# DoubleMotorSwitch.net
KiCad netlist of a schematic drawn in EAGLE
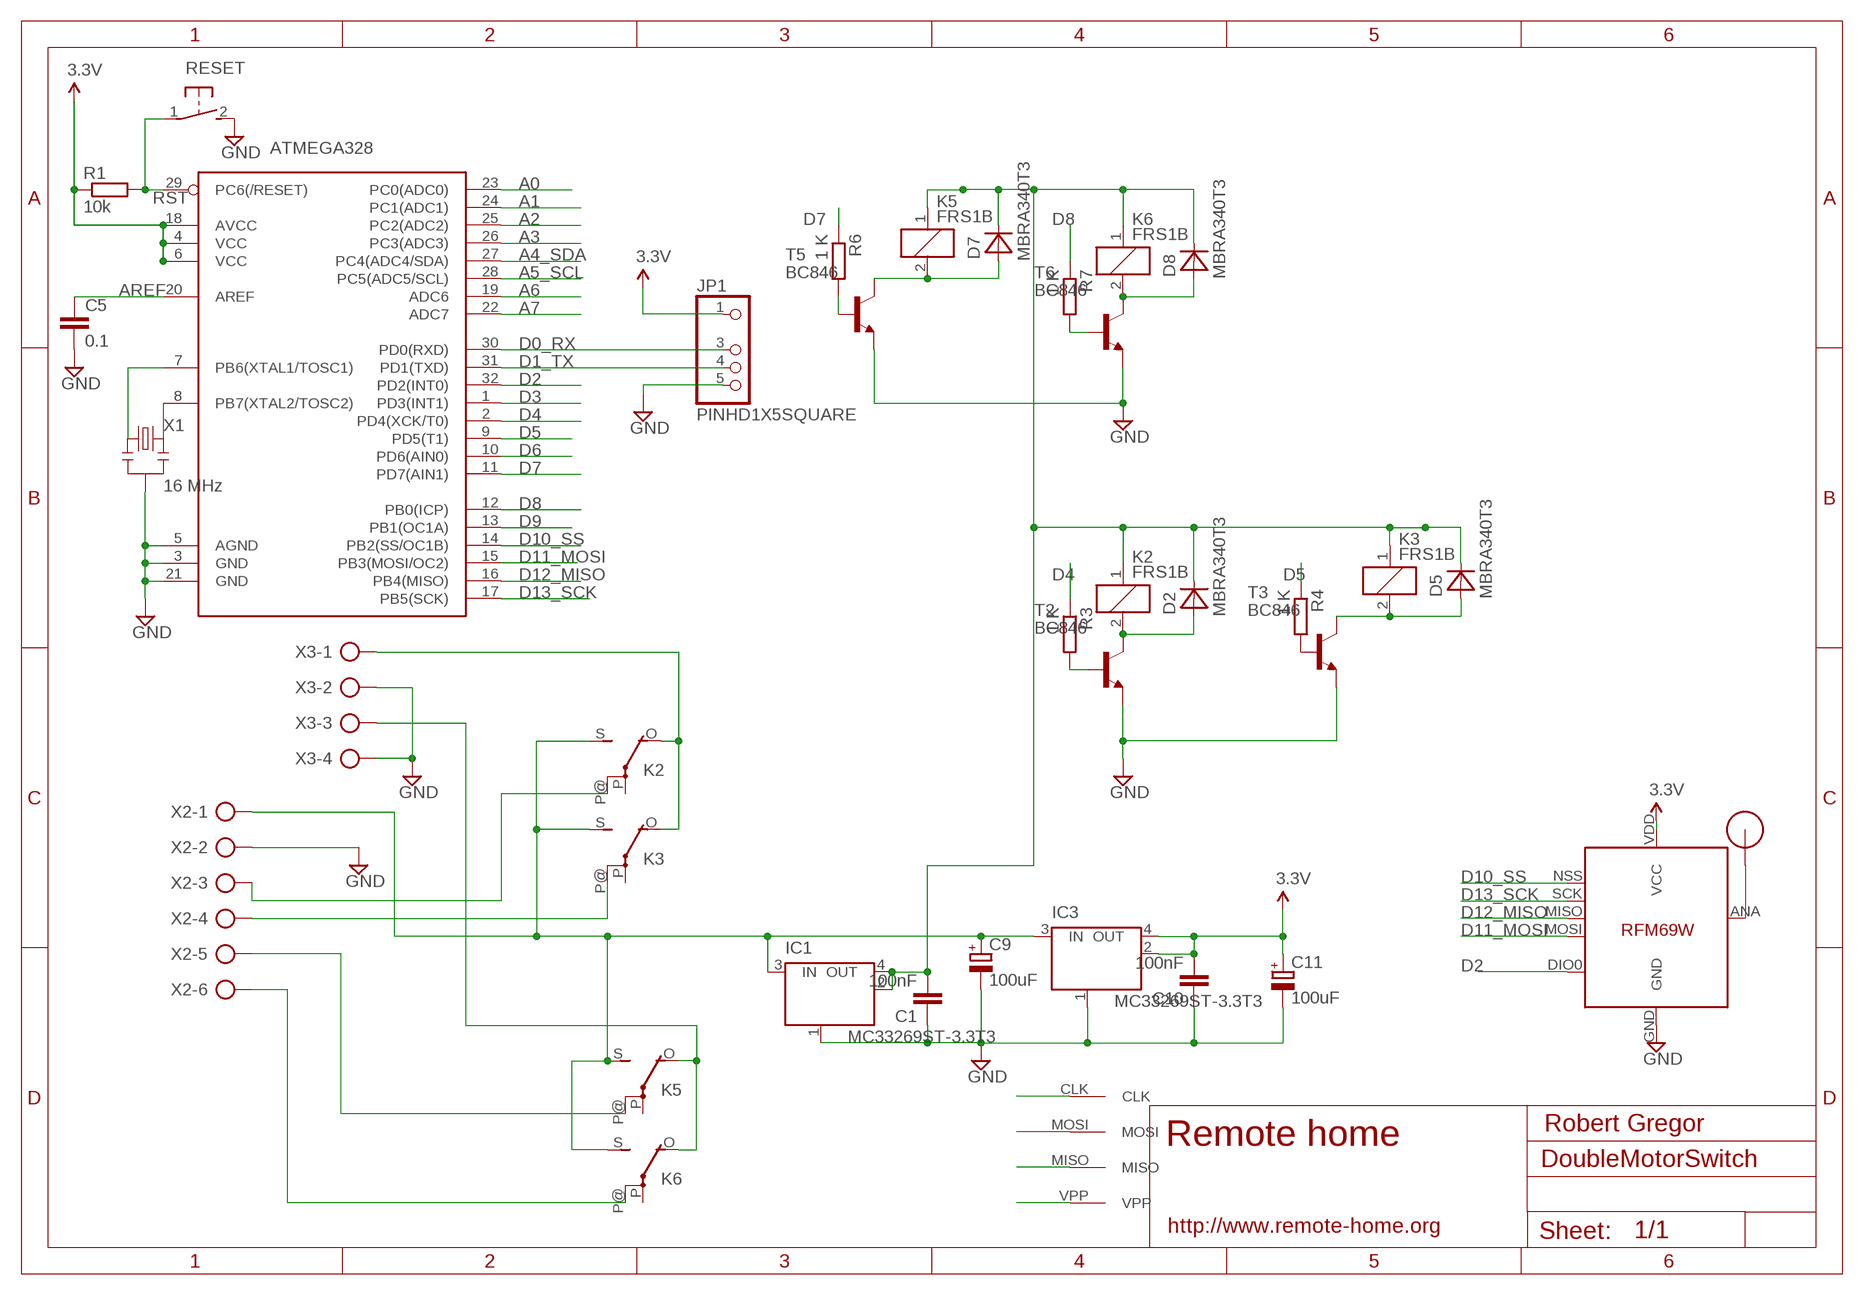
[diagram p0: schematic, sheet 1]

(export (version "E")
  (design (tool "Eeschema 10.0.6"))
  (components
    (comp (ref "ATMEGA328")
      (value "ATMega-328")
      (footprint "eagle-import:TQFP32-08")
      (libsource (lib "eagle-import") (part "ATMEGA168/328TQFP32"))
    )
    (comp (ref "C1")
      (value "100nF")
      (footprint "eagle-import:C2012")
      (libsource (lib "eagle-import") (part "C-EUC2012"))
    )
    (comp (ref "C5")
      (value "0.1")
      (footprint "eagle-import:C2012")
      (libsource (lib "eagle-import") (part "C-EUC2012"))
    )
    (comp (ref "C9")
      (value "100uF")
      (footprint "eagle-import:SMC_B")
      (libsource (lib "eagle-import") (part "CPOL-EUSMCB"))
    )
    (comp (ref "C10")
      (value "100nF")
      (footprint "eagle-import:C2012")
      (libsource (lib "eagle-import") (part "C-EUC2012"))
    )
    (comp (ref "C11")
      (value "100uF")
      (footprint "eagle-import:SMC_B")
      (libsource (lib "eagle-import") (part "CPOL-EUSMCB"))
    )
    (comp (ref "D2")
      (value "MBRA340T3")
      (footprint "eagle-import:SMA")
      (libsource (lib "eagle-import") (part "MBRA340T3"))
    )
    (comp (ref "D5")
      (value "MBRA340T3")
      (footprint "eagle-import:SMA")
      (libsource (lib "eagle-import") (part "MBRA340T3"))
    )
    (comp (ref "D7")
      (value "MBRA340T3")
      (footprint "eagle-import:SMA")
      (libsource (lib "eagle-import") (part "MBRA340T3"))
    )
    (comp (ref "D8")
      (value "MBRA340T3")
      (footprint "eagle-import:SMA")
      (libsource (lib "eagle-import") (part "MBRA340T3"))
    )
    (comp (ref "IC1")
      (value "MC33269ST-3.3T3")
      (footprint "eagle-import:SOT223")
      (libsource (lib "eagle-import") (part "MC33269ST-3.3T3"))
    )
    (comp (ref "IC3")
      (value "MC33269ST-3.3T3")
      (footprint "eagle-import:SOT223")
      (libsource (lib "eagle-import") (part "MC33269ST-3.3T3"))
    )
    (comp (ref "JP1")
      (value "PINHD1X5SQUARE")
      (footprint "eagle-import:PINHD1X05-SQUARE")
      (libsource (lib "eagle-import") (part "PINHD1X5SQUARE"))
    )
    (comp (ref "K2")
      (value "FRS1B")
      (footprint "eagle-import:FRS1B")
      (libsource (lib "eagle-import") (part "FRS1B"))
    )
    (comp (ref "K3")
      (value "FRS1B")
      (footprint "eagle-import:FRS1B")
      (libsource (lib "eagle-import") (part "FRS1B"))
    )
    (comp (ref "K5")
      (value "FRS1B")
      (footprint "eagle-import:FRS1B")
      (libsource (lib "eagle-import") (part "FRS1B"))
    )
    (comp (ref "K6")
      (value "FRS1B")
      (footprint "eagle-import:FRS1B")
      (libsource (lib "eagle-import") (part "FRS1B"))
    )
    (comp (ref "R1")
      (value "10k")
      (footprint "eagle-import:R2012")
      (libsource (lib "eagle-import") (part "R-EU_R2012"))
    )
    (comp (ref "R3")
      (value "1 K")
      (footprint "eagle-import:M2012")
      (libsource (lib "eagle-import") (part "R-EU_M2012"))
    )
    (comp (ref "R4")
      (value "1 K")
      (footprint "eagle-import:M2012")
      (libsource (lib "eagle-import") (part "R-EU_M2012"))
    )
    (comp (ref "R6")
      (value "1 K")
      (footprint "eagle-import:M2012")
      (libsource (lib "eagle-import") (part "R-EU_M2012"))
    )
    (comp (ref "R7")
      (value "1 K")
      (footprint "eagle-import:M2012")
      (libsource (lib "eagle-import") (part "R-EU_M2012"))
    )
    (comp (ref "RESET")
      (value "DTSM-3")
      (footprint "eagle-import:DTSM-3")
      (libsource (lib "eagle-import") (part "DTSM-3"))
    )
    (comp (ref "T2")
      (value "BC846")
      (footprint "eagle-import:SOT23")
      (libsource (lib "eagle-import") (part "BC846"))
    )
    (comp (ref "T3")
      (value "BC846")
      (footprint "eagle-import:SOT23")
      (libsource (lib "eagle-import") (part "BC846"))
    )
    (comp (ref "T5")
      (value "BC846")
      (footprint "eagle-import:SOT23")
      (libsource (lib "eagle-import") (part "BC846"))
    )
    (comp (ref "T6")
      (value "BC846")
      (footprint "eagle-import:SOT23")
      (libsource (lib "eagle-import") (part "BC846"))
    )
    (comp (ref "U$1")
      (value "RFM12B_ANTENNA")
      (footprint "eagle-import:RFM12B-ANTENNA")
      (libsource (lib "eagle-import") (part "RFM12B_ANTENNA"))
    )
    (comp (ref "U$2")
      (value "AVRHEADERDIP")
      (footprint "eagle-import:AVRHEADER")
      (libsource (lib "eagle-import") (part "AVRHEADERDIP"))
    )
    (comp (ref "U$5")
      (value "RFM69")
      (footprint "eagle-import:RFM69W-MINPADS")
      (libsource (lib "eagle-import") (part "RFM69"))
    )
    (comp (ref "X1")
      (value "16 MHz")
      (footprint "eagle-import:RESONATOR-SMD")
      (libsource (lib "eagle-import") (part "RESONATORSMD"))
    )
    (comp (ref "X2")
      (value "AK500/6")
      (footprint "eagle-import:AK500_6")
      (libsource (lib "eagle-import") (part "AK500/6"))
    )
    (comp (ref "X3")
      (value "AK500/4")
      (footprint "eagle-import:AK500_4")
      (libsource (lib "eagle-import") (part "AK500/4"))
    )
  )
  (nets
    (net (code "1") (name "/A0") (class "Default")
      (node (ref "ATMEGA328") (pin "23") (pinfunction "PC0(ADC0)_23") (pintype "bidirectional"))
    )
    (net (code "2") (name "/A1") (class "Default")
      (node (ref "ATMEGA328") (pin "24") (pinfunction "PC1(ADC1)_24") (pintype "bidirectional"))
    )
    (net (code "3") (name "/A2") (class "Default")
      (node (ref "ATMEGA328") (pin "25") (pinfunction "PC2(ADC2)_25") (pintype "bidirectional"))
    )
    (net (code "4") (name "/A3") (class "Default")
      (node (ref "ATMEGA328") (pin "26") (pinfunction "PC3(ADC3)_26") (pintype "bidirectional"))
    )
    (net (code "5") (name "/A4_SDA") (class "Default")
      (node (ref "ATMEGA328") (pin "27") (pinfunction "PC4(ADC4/SDA)_27") (pintype "bidirectional"))
    )
    (net (code "6") (name "/A5_SCL") (class "Default")
      (node (ref "ATMEGA328") (pin "28") (pinfunction "PC5(ADC5/SCL)_28") (pintype "bidirectional"))
    )
    (net (code "7") (name "/A6") (class "Default")
      (node (ref "ATMEGA328") (pin "19") (pinfunction "ADC6_19") (pintype "bidirectional"))
    )
    (net (code "8") (name "/A7") (class "Default")
      (node (ref "ATMEGA328") (pin "22") (pinfunction "ADC7_22") (pintype "bidirectional"))
    )
    (net (code "9") (name "/AREF") (class "Default")
      (node (ref "ATMEGA328") (pin "20") (pinfunction "AREF_20") (pintype "bidirectional"))
      (node (ref "C5") (pin "1") (pinfunction "1_1") (pintype "passive"))
    )
    (net (code "10") (name "/D0_RX") (class "Default")
      (node (ref "ATMEGA328") (pin "30") (pinfunction "PD0(RXD)_30") (pintype "bidirectional"))
      (node (ref "JP1") (pin "3") (pinfunction "3_3") (pintype "passive"))
    )
    (net (code "11") (name "/D1_TX") (class "Default")
      (node (ref "ATMEGA328") (pin "31") (pinfunction "PD1(TXD)_31") (pintype "bidirectional"))
      (node (ref "JP1") (pin "4") (pinfunction "4_4") (pintype "passive"))
    )
    (net (code "12") (name "/D2") (class "Default")
      (node (ref "ATMEGA328") (pin "32") (pinfunction "PD2(INT0)_32") (pintype "bidirectional"))
      (node (ref "U$5") (pin "DIO0") (pinfunction "DIO0_DIO0") (pintype "open_collector"))
    )
    (net (code "13") (name "/D3") (class "Default")
      (node (ref "ATMEGA328") (pin "1") (pinfunction "PD3(INT1)_1") (pintype "bidirectional"))
    )
    (net (code "14") (name "/D4") (class "Default")
      (node (ref "ATMEGA328") (pin "2") (pinfunction "PD4(XCK/T0)_2") (pintype "bidirectional"))
      (node (ref "R3") (pin "1") (pinfunction "1_1") (pintype "passive"))
    )
    (net (code "15") (name "/D5") (class "Default")
      (node (ref "ATMEGA328") (pin "9") (pinfunction "PD5(T1)_9") (pintype "bidirectional"))
      (node (ref "R4") (pin "1") (pinfunction "1_1") (pintype "passive"))
    )
    (net (code "16") (name "/D6") (class "Default")
      (node (ref "ATMEGA328") (pin "10") (pinfunction "PD6(AIN0)_10") (pintype "bidirectional"))
    )
    (net (code "17") (name "/D7") (class "Default")
      (node (ref "ATMEGA328") (pin "11") (pinfunction "PD7(AIN1)_11") (pintype "bidirectional"))
      (node (ref "R6") (pin "1") (pinfunction "1_1") (pintype "passive"))
    )
    (net (code "18") (name "/D8") (class "Default")
      (node (ref "ATMEGA328") (pin "12") (pinfunction "PB0(ICP)_12") (pintype "bidirectional"))
      (node (ref "R7") (pin "1") (pinfunction "1_1") (pintype "passive"))
    )
    (net (code "19") (name "/D9") (class "Default")
      (node (ref "ATMEGA328") (pin "13") (pinfunction "PB1(OC1A)_13") (pintype "bidirectional"))
    )
    (net (code "20") (name "/D10_SS") (class "Default")
      (node (ref "ATMEGA328") (pin "14") (pinfunction "PB2(SS/OC1B)_14") (pintype "bidirectional"))
      (node (ref "U$5") (pin "NSS") (pinfunction "SEL_NSS") (pintype "input"))
    )
    (net (code "21") (name "/D11_MOSI") (class "Default")
      (node (ref "ATMEGA328") (pin "15") (pinfunction "PB3(MOSI/OC2)_15") (pintype "bidirectional"))
      (node (ref "U$2") (pin "MOSI") (pinfunction "MOSI_MOSI") (pintype "bidirectional"))
      (node (ref "U$5") (pin "MOSI") (pinfunction "MOSI_MOSI") (pintype "output"))
    )
    (net (code "22") (name "/D12_MISO") (class "Default")
      (node (ref "ATMEGA328") (pin "16") (pinfunction "PB4(MISO)_16") (pintype "bidirectional"))
      (node (ref "U$2") (pin "MISO") (pinfunction "MISO_MISO") (pintype "bidirectional"))
      (node (ref "U$5") (pin "MISO") (pinfunction "MISO_MISO") (pintype "input"))
    )
    (net (code "23") (name "/D13_SCK") (class "Default")
      (node (ref "ATMEGA328") (pin "17") (pinfunction "PB5(SCK)_17") (pintype "bidirectional"))
      (node (ref "U$2") (pin "CLK") (pinfunction "CLK_CLK") (pintype "bidirectional"))
      (node (ref "U$5") (pin "SCK") (pinfunction "SCK_SCK") (pintype "input"))
    )
    (net (code "24") (name "/RST") (class "Default")
      (node (ref "ATMEGA328") (pin "29") (pinfunction "PC6(/RESET)_29") (pintype "bidirectional"))
      (node (ref "R1") (pin "2") (pinfunction "2_2") (pintype "passive"))
      (node (ref "RESET") (pin "1") (pinfunction "1_1") (pintype "passive"))
      (node (ref "U$2") (pin "VPP") (pinfunction "VPP_VPP") (pintype "bidirectional"))
    )
    (net (code "25") (name "3.3V") (class "Default")
      (node (ref "ATMEGA328") (pin "18") (pinfunction "AVCC_18") (pintype "bidirectional"))
      (node (ref "ATMEGA328") (pin "4") (pinfunction "VCC_4") (pintype "bidirectional"))
      (node (ref "ATMEGA328") (pin "6") (pinfunction "VCC_6") (pintype "bidirectional"))
      (node (ref "C10") (pin "2") (pinfunction "2_2") (pintype "passive"))
      (node (ref "C11") (pin "+") (pinfunction "+_+") (pintype "passive"))
      (node (ref "IC3") (pin "2") (pinfunction "OUT_2") (pintype "passive"))
      (node (ref "IC3") (pin "4") (pinfunction "OUT_4") (pintype "passive"))
      (node (ref "JP1") (pin "1") (pinfunction "1_1") (pintype "passive"))
      (node (ref "R1") (pin "1") (pinfunction "1_1") (pintype "passive"))
      (node (ref "U$5") (pin "VDD") (pinfunction "VCC_VDD") (pintype "power_in"))
    )
    (net (code "26") (name "GND") (class "Default")
      (node (ref "ATMEGA328") (pin "21") (pinfunction "GND_21") (pintype "bidirectional"))
      (node (ref "ATMEGA328") (pin "3") (pinfunction "GND_3") (pintype "bidirectional"))
      (node (ref "ATMEGA328") (pin "5") (pinfunction "AGND_5") (pintype "bidirectional"))
      (node (ref "C1") (pin "1") (pinfunction "1_1") (pintype "passive"))
      (node (ref "C10") (pin "1") (pinfunction "1_1") (pintype "passive"))
      (node (ref "C11") (pin "-") (pinfunction "-_-") (pintype "passive"))
      (node (ref "C5") (pin "2") (pinfunction "2_2") (pintype "passive"))
      (node (ref "C9") (pin "-") (pinfunction "-_-") (pintype "passive"))
      (node (ref "IC1") (pin "1") (pinfunction "GND/ADJ_1") (pintype "input"))
      (node (ref "IC3") (pin "1") (pinfunction "GND/ADJ_1") (pintype "input"))
      (node (ref "JP1") (pin "5") (pinfunction "5_5") (pintype "passive"))
      (node (ref "RESET") (pin "2") (pinfunction "2_2") (pintype "passive"))
      (node (ref "T2") (pin "2") (pinfunction "E_2") (pintype "passive"))
      (node (ref "T3") (pin "2") (pinfunction "E_2") (pintype "passive"))
      (node (ref "T5") (pin "2") (pinfunction "E_2") (pintype "passive"))
      (node (ref "T6") (pin "2") (pinfunction "E_2") (pintype "passive"))
      (node (ref "U$5") (pin "GND") (pinfunction "GND_GND") (pintype "power_in"))
      (node (ref "X1") (pin "2") (pinfunction "2_2") (pintype "passive"))
      (node (ref "X2") (pin "2") (pinfunction "KL_2") (pintype "passive"))
      (node (ref "X3") (pin "2") (pinfunction "KL_2") (pintype "passive"))
      (node (ref "X3") (pin "4") (pinfunction "KL_4") (pintype "passive"))
    )
    (net (code "27") (name "Net-(ATMEGA328-PB6(XTAL1{slash}TOSC1))") (class "Default")
      (node (ref "ATMEGA328") (pin "7") (pinfunction "PB6(XTAL1/TOSC1)_7") (pintype "bidirectional"))
      (node (ref "X1") (pin "1") (pinfunction "1_1") (pintype "passive"))
    )
    (net (code "28") (name "Net-(ATMEGA328-PB7(XTAL2{slash}TOSC2))") (class "Default")
      (node (ref "ATMEGA328") (pin "8") (pinfunction "PB7(XTAL2/TOSC2)_8") (pintype "bidirectional"))
      (node (ref "X1") (pin "3") (pinfunction "3_3") (pintype "passive"))
    )
    (net (code "29") (name "Net-(C1-Pad2)") (class "Default")
      (node (ref "C1") (pin "2") (pinfunction "2_2") (pintype "passive"))
      (node (ref "D2") (pin "C") (pinfunction "C_C") (pintype "passive"))
      (node (ref "D5") (pin "C") (pinfunction "C_C") (pintype "passive"))
      (node (ref "D7") (pin "C") (pinfunction "C_C") (pintype "passive"))
      (node (ref "D8") (pin "C") (pinfunction "C_C") (pintype "passive"))
      (node (ref "IC1") (pin "2") (pinfunction "OUT_2") (pintype "passive"))
      (node (ref "IC1") (pin "4") (pinfunction "OUT_4") (pintype "passive"))
      (node (ref "K2") (pin "1") (pinfunction "1_1") (pintype "passive"))
      (node (ref "K3") (pin "1") (pinfunction "1_1") (pintype "passive"))
      (node (ref "K5") (pin "1") (pinfunction "1_1") (pintype "passive"))
      (node (ref "K6") (pin "1") (pinfunction "1_1") (pintype "passive"))
    )
    (net (code "30") (name "Net-(IC1-IN)") (class "Default")
      (node (ref "C9") (pin "+") (pinfunction "+_+") (pintype "passive"))
      (node (ref "IC1") (pin "3") (pinfunction "IN_3") (pintype "input"))
      (node (ref "IC3") (pin "3") (pinfunction "IN_3") (pintype "input"))
      (node (ref "K2") (pin "S") (pinfunction "S_S") (pintype "passive"))
      (node (ref "K3") (pin "S") (pinfunction "S_S") (pintype "passive"))
      (node (ref "K5") (pin "S") (pinfunction "S_S") (pintype "passive"))
      (node (ref "K6") (pin "S") (pinfunction "S_S") (pintype "passive"))
      (node (ref "X2") (pin "1") (pinfunction "KL_1") (pintype "passive"))
    )
    (net (code "31") (name "Net-(T2-B)") (class "Default")
      (node (ref "R3") (pin "2") (pinfunction "2_2") (pintype "passive"))
      (node (ref "T2") (pin "1") (pinfunction "B_1") (pintype "passive"))
    )
    (net (code "32") (name "Net-(T2-C)") (class "Default")
      (node (ref "D2") (pin "A") (pinfunction "A_A") (pintype "passive"))
      (node (ref "K2") (pin "2") (pinfunction "2_2") (pintype "passive"))
      (node (ref "T2") (pin "3") (pinfunction "C_3") (pintype "passive"))
    )
    (net (code "33") (name "Net-(T3-B)") (class "Default")
      (node (ref "R4") (pin "2") (pinfunction "2_2") (pintype "passive"))
      (node (ref "T3") (pin "1") (pinfunction "B_1") (pintype "passive"))
    )
    (net (code "34") (name "Net-(T3-C)") (class "Default")
      (node (ref "D5") (pin "A") (pinfunction "A_A") (pintype "passive"))
      (node (ref "K3") (pin "2") (pinfunction "2_2") (pintype "passive"))
      (node (ref "T3") (pin "3") (pinfunction "C_3") (pintype "passive"))
    )
    (net (code "35") (name "Net-(T5-B)") (class "Default")
      (node (ref "R6") (pin "2") (pinfunction "2_2") (pintype "passive"))
      (node (ref "T5") (pin "1") (pinfunction "B_1") (pintype "passive"))
    )
    (net (code "36") (name "Net-(T5-C)") (class "Default")
      (node (ref "D7") (pin "A") (pinfunction "A_A") (pintype "passive"))
      (node (ref "K5") (pin "2") (pinfunction "2_2") (pintype "passive"))
      (node (ref "T5") (pin "3") (pinfunction "C_3") (pintype "passive"))
    )
    (net (code "37") (name "Net-(T6-B)") (class "Default")
      (node (ref "R7") (pin "2") (pinfunction "2_2") (pintype "passive"))
      (node (ref "T6") (pin "1") (pinfunction "B_1") (pintype "passive"))
    )
    (net (code "38") (name "Net-(T6-C)") (class "Default")
      (node (ref "D8") (pin "A") (pinfunction "A_A") (pintype "passive"))
      (node (ref "K6") (pin "2") (pinfunction "2_2") (pintype "passive"))
      (node (ref "T6") (pin "3") (pinfunction "C_3") (pintype "passive"))
    )
    (net (code "39") (name "Net-(U$1-1)") (class "Default")
      (node (ref "U$1") (pin "P$1") (pinfunction "1_P$1") (pintype "bidirectional"))
      (node (ref "U$5") (pin "ANA") (pinfunction "ANT_ANA") (pintype "passive"))
    )
    (net (code "40") (name "Net-(X2C-KL)") (class "Default")
      (node (ref "K2") (pin "P@") (pinfunction "P_P@") (pintype "passive"))
      (node (ref "X2") (pin "3") (pinfunction "KL_3") (pintype "passive"))
    )
    (net (code "41") (name "Net-(X2D-KL)") (class "Default")
      (node (ref "K3") (pin "P@") (pinfunction "P_P@") (pintype "passive"))
      (node (ref "X2") (pin "4") (pinfunction "KL_4") (pintype "passive"))
    )
    (net (code "42") (name "Net-(X2E-KL)") (class "Default")
      (node (ref "K5") (pin "P@") (pinfunction "P_P@") (pintype "passive"))
      (node (ref "X2") (pin "5") (pinfunction "KL_5") (pintype "passive"))
    )
    (net (code "43") (name "Net-(X2F-KL)") (class "Default")
      (node (ref "K6") (pin "P@") (pinfunction "P_P@") (pintype "passive"))
      (node (ref "X2") (pin "6") (pinfunction "KL_6") (pintype "passive"))
    )
    (net (code "44") (name "Net-(X3A-KL)") (class "Default")
      (node (ref "K2") (pin "O") (pinfunction "O_O") (pintype "passive"))
      (node (ref "K3") (pin "O") (pinfunction "O_O") (pintype "passive"))
      (node (ref "X3") (pin "1") (pinfunction "KL_1") (pintype "passive"))
    )
    (net (code "45") (name "Net-(X3C-KL)") (class "Default")
      (node (ref "K5") (pin "O") (pinfunction "O_O") (pintype "passive"))
      (node (ref "K6") (pin "O") (pinfunction "O_O") (pintype "passive"))
      (node (ref "X3") (pin "3") (pinfunction "KL_3") (pintype "passive"))
    )
    (net (code "46") (name "unconnected-(K2-PadP)") (class "Default")
      (node (ref "K2") (pin "P") (pinfunction "P_P") (pintype "passive"))
    )
    (net (code "47") (name "unconnected-(K3-PadP)") (class "Default")
      (node (ref "K3") (pin "P") (pinfunction "P_P") (pintype "passive"))
    )
    (net (code "48") (name "unconnected-(K5-PadP)") (class "Default")
      (node (ref "K5") (pin "P") (pinfunction "P_P") (pintype "passive"))
    )
    (net (code "49") (name "unconnected-(K6-PadP)") (class "Default")
      (node (ref "K6") (pin "P") (pinfunction "P_P") (pintype "passive"))
    )
  )
)
